# offsets.net
KiCad netlist of a schematic drawn in EAGLE
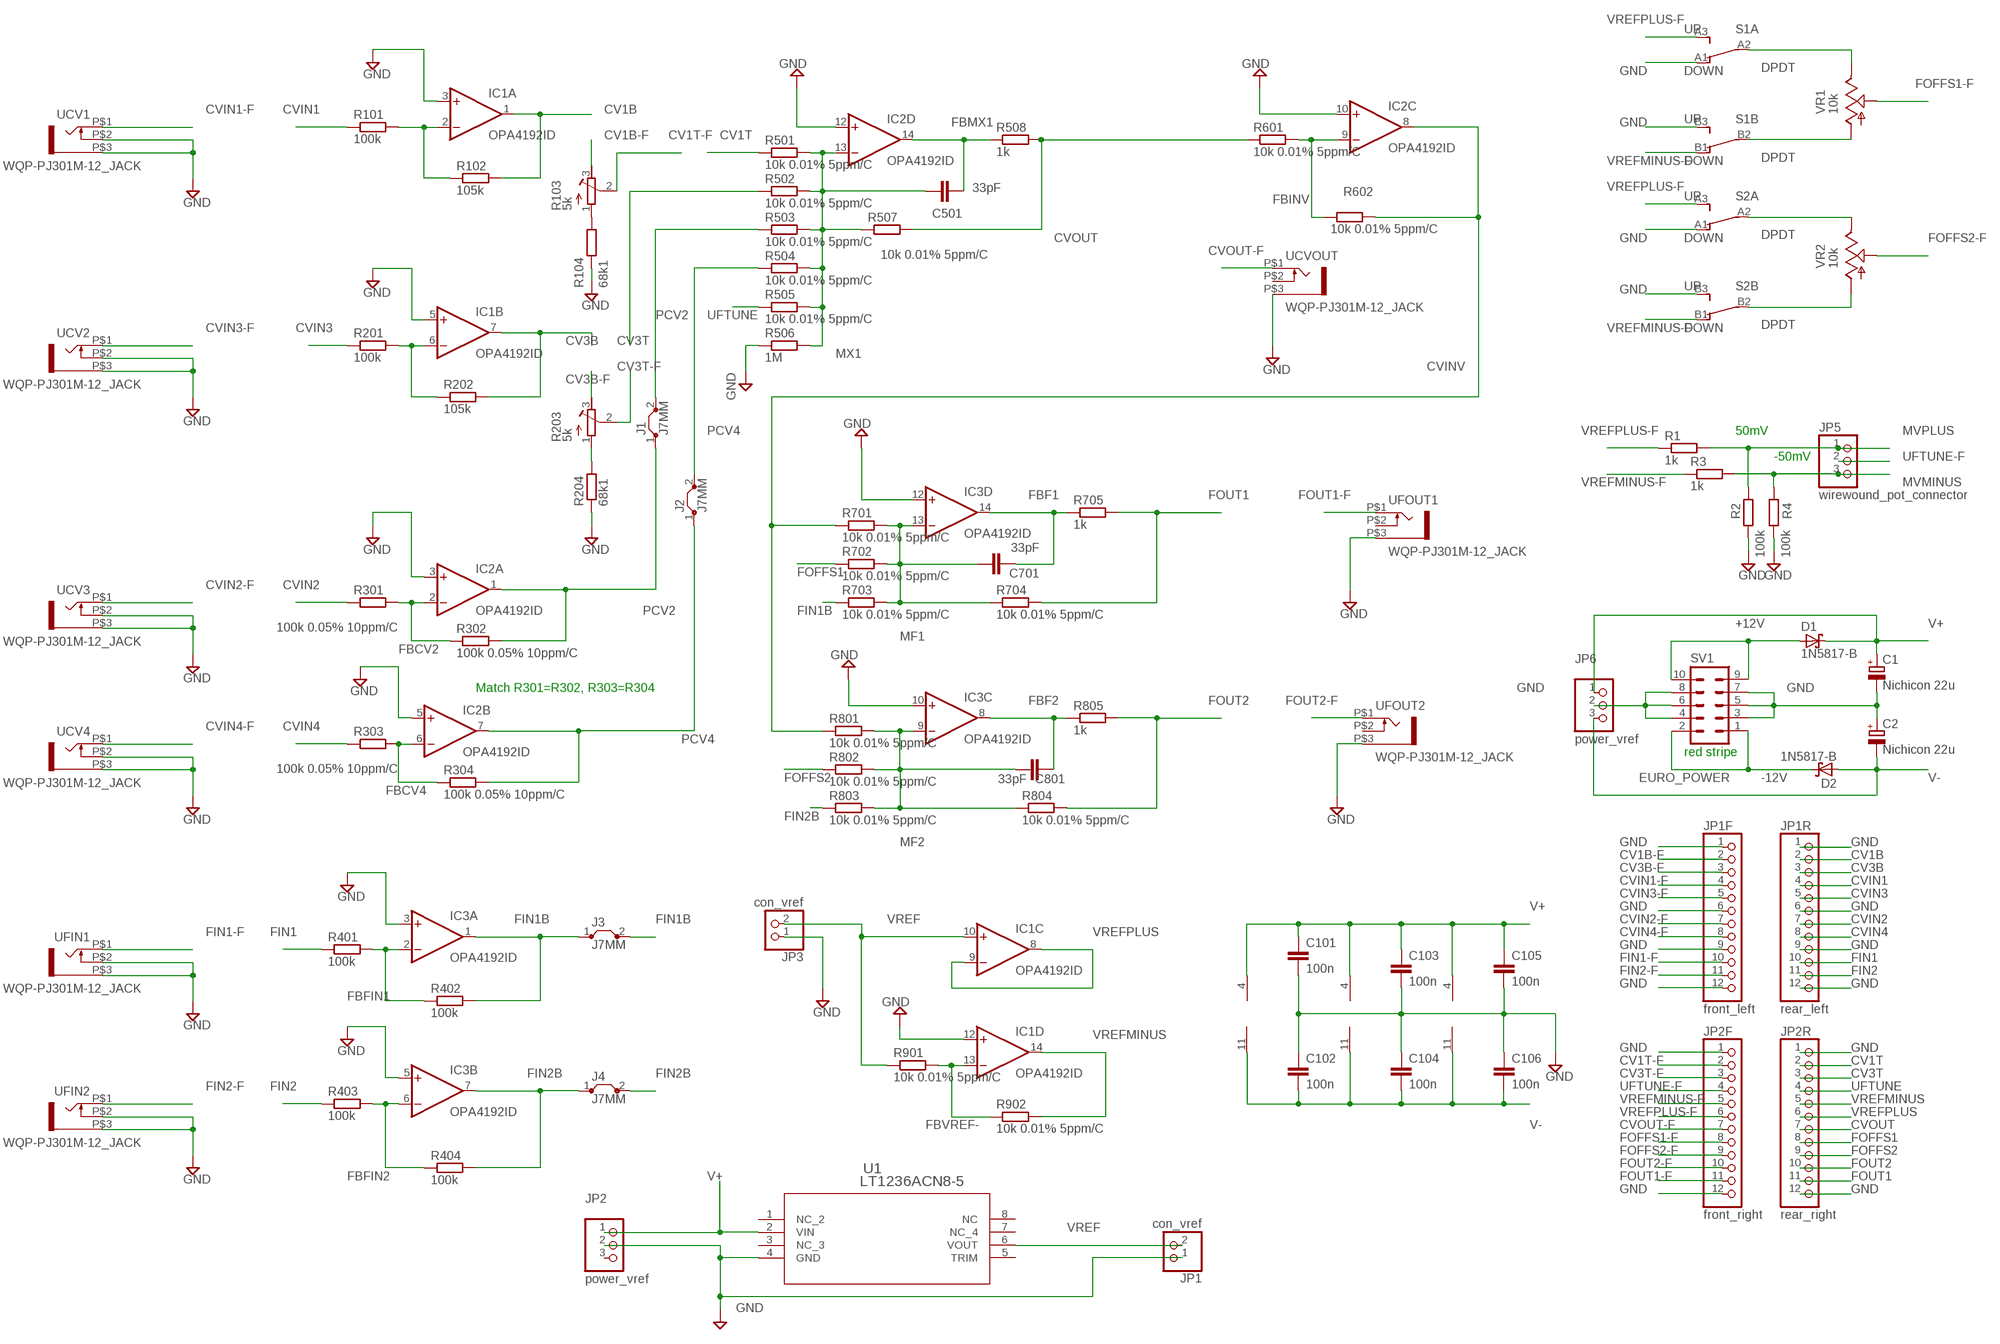
[diagram p0: schematic, sheet 1]

(export (version "E")
  (design (tool "Eeschema 10.0.6"))
  (components
    (comp (ref "C1")
      (value "Nichicon 22u")
      (footprint "eagle-import:E2,5-5")
      (libsource (lib "eagle-import") (part "CPOL-EUE2.5-5"))
    )
    (comp (ref "C2")
      (value "Nichicon 22u")
      (footprint "eagle-import:E2,5-5")
      (libsource (lib "eagle-import") (part "CPOL-EUE2.5-5"))
    )
    (comp (ref "C101")
      (value "100n")
      (footprint "eagle-import:C1206")
      (libsource (lib "eagle-import") (part "C-EUC1206"))
    )
    (comp (ref "C102")
      (value "100n")
      (footprint "eagle-import:C1206")
      (libsource (lib "eagle-import") (part "C-EUC1206"))
    )
    (comp (ref "C103")
      (value "100n")
      (footprint "eagle-import:C1206")
      (libsource (lib "eagle-import") (part "C-EUC1206"))
    )
    (comp (ref "C104")
      (value "100n")
      (footprint "eagle-import:C1206")
      (libsource (lib "eagle-import") (part "C-EUC1206"))
    )
    (comp (ref "C105")
      (value "100n")
      (footprint "eagle-import:C1206")
      (libsource (lib "eagle-import") (part "C-EUC1206"))
    )
    (comp (ref "C106")
      (value "100n")
      (footprint "eagle-import:C1206")
      (libsource (lib "eagle-import") (part "C-EUC1206"))
    )
    (comp (ref "C501")
      (value "33pF")
      (footprint "eagle-import:C0805K")
      (libsource (lib "eagle-import") (part "C-EUC0805K"))
    )
    (comp (ref "C701")
      (value "33pF")
      (footprint "eagle-import:C0805K")
      (libsource (lib "eagle-import") (part "C-EUC0805K"))
    )
    (comp (ref "C801")
      (value "33pF")
      (footprint "eagle-import:C0805K")
      (libsource (lib "eagle-import") (part "C-EUC0805K"))
    )
    (comp (ref "D1")
      (value "1N5817-B")
      (footprint "eagle-import:DO41-7.6")
      (libsource (lib "eagle-import") (part "1N5817-B"))
    )
    (comp (ref "D2")
      (value "1N5817-B")
      (footprint "eagle-import:DO41-7.6")
      (libsource (lib "eagle-import") (part "1N5817-B"))
    )
    (comp (ref "IC1")
      (value "OPA4192ID")
      (footprint "eagle-import:SO14")
      (libsource (lib "eagle-import") (part "TL074D"))
    )
    (comp (ref "IC2")
      (value "OPA4192ID")
      (footprint "eagle-import:SO14")
      (libsource (lib "eagle-import") (part "TL074D"))
    )
    (comp (ref "IC3")
      (value "OPA4192ID")
      (footprint "eagle-import:SO14")
      (libsource (lib "eagle-import") (part "TL074D"))
    )
    (comp (ref "J1")
      (value "J7MM")
      (footprint "eagle-import:07")
      (libsource (lib "eagle-import") (part "J7MM"))
    )
    (comp (ref "J2")
      (value "J7MM")
      (footprint "eagle-import:07")
      (libsource (lib "eagle-import") (part "J7MM"))
    )
    (comp (ref "J3")
      (value "J7MM")
      (footprint "eagle-import:07")
      (libsource (lib "eagle-import") (part "J7MM"))
    )
    (comp (ref "J4")
      (value "J7MM")
      (footprint "eagle-import:07")
      (libsource (lib "eagle-import") (part "J7MM"))
    )
    (comp (ref "JP1")
      (value "con_vref")
      (footprint "eagle-import:1X02")
      (libsource (lib "eagle-import") (part "PINHD-1X2"))
    )
    (comp (ref "JP1F")
      (value "front_left")
      (footprint "eagle-import:1X12")
      (libsource (lib "eagle-import") (part "PINHD-1X12"))
    )
    (comp (ref "JP1R")
      (value "rear_left")
      (footprint "eagle-import:1X12")
      (libsource (lib "eagle-import") (part "PINHD-1X12"))
    )
    (comp (ref "JP2")
      (value "power_vref")
      (footprint "eagle-import:1X03")
      (libsource (lib "eagle-import") (part "PINHD-1X3"))
    )
    (comp (ref "JP2F")
      (value "front_right")
      (footprint "eagle-import:1X12")
      (libsource (lib "eagle-import") (part "PINHD-1X12"))
    )
    (comp (ref "JP2R")
      (value "rear_right")
      (footprint "eagle-import:1X12")
      (libsource (lib "eagle-import") (part "PINHD-1X12"))
    )
    (comp (ref "JP3")
      (value "con_vref")
      (footprint "eagle-import:1X02")
      (libsource (lib "eagle-import") (part "PINHD-1X2"))
    )
    (comp (ref "JP5")
      (value "wirewound_pot_connector")
      (footprint "eagle-import:1X03")
      (libsource (lib "eagle-import") (part "PINHD-1X3"))
    )
    (comp (ref "JP6")
      (value "power_vref")
      (footprint "eagle-import:1X03")
      (libsource (lib "eagle-import") (part "PINHD-1X3"))
    )
    (comp (ref "R1")
      (value "1k")
      (footprint "eagle-import:R0805W")
      (libsource (lib "eagle-import") (part "R-EU_R0805W"))
    )
    (comp (ref "R2")
      (value "100k")
      (footprint "eagle-import:R0805W")
      (libsource (lib "eagle-import") (part "R-EU_R0805W"))
    )
    (comp (ref "R3")
      (value "1k")
      (footprint "eagle-import:R0805W")
      (libsource (lib "eagle-import") (part "R-EU_R0805W"))
    )
    (comp (ref "R4")
      (value "100k")
      (footprint "eagle-import:R0805W")
      (libsource (lib "eagle-import") (part "R-EU_R0805W"))
    )
    (comp (ref "R101")
      (value "100k")
      (footprint "eagle-import:R0805W")
      (libsource (lib "eagle-import") (part "R-EU_R0805W"))
    )
    (comp (ref "R102")
      (value "105k")
      (footprint "eagle-import:R0805W")
      (libsource (lib "eagle-import") (part "R-EU_R0805W"))
    )
    (comp (ref "R103")
      (value "5k")
      (footprint "eagle-import:RTRIM3296W")
      (libsource (lib "eagle-import") (part "R-TRIMM3296W"))
    )
    (comp (ref "R104")
      (value "68k1")
      (footprint "eagle-import:R0805W")
      (libsource (lib "eagle-import") (part "R-EU_R0805W"))
    )
    (comp (ref "R201")
      (value "100k")
      (footprint "eagle-import:R0805W")
      (libsource (lib "eagle-import") (part "R-EU_R0805W"))
    )
    (comp (ref "R202")
      (value "105k")
      (footprint "eagle-import:R0805W")
      (libsource (lib "eagle-import") (part "R-EU_R0805W"))
    )
    (comp (ref "R203")
      (value "5k")
      (footprint "eagle-import:RTRIM3296W")
      (libsource (lib "eagle-import") (part "R-TRIMM3296W"))
    )
    (comp (ref "R204")
      (value "68k1")
      (footprint "eagle-import:R0805W")
      (libsource (lib "eagle-import") (part "R-EU_R0805W"))
    )
    (comp (ref "R301")
      (value "100k 0.05% 10ppm/C")
      (footprint "eagle-import:R0805W")
      (libsource (lib "eagle-import") (part "R-EU_R0805W"))
    )
    (comp (ref "R302")
      (value "100k 0.05% 10ppm/C")
      (footprint "eagle-import:R0805W")
      (libsource (lib "eagle-import") (part "R-EU_R0805W"))
    )
    (comp (ref "R303")
      (value "100k 0.05% 10ppm/C")
      (footprint "eagle-import:R0805W")
      (libsource (lib "eagle-import") (part "R-EU_R0805W"))
    )
    (comp (ref "R304")
      (value "100k 0.05% 10ppm/C")
      (footprint "eagle-import:R0805W")
      (libsource (lib "eagle-import") (part "R-EU_R0805W"))
    )
    (comp (ref "R401")
      (value "100k")
      (footprint "eagle-import:R0805W")
      (libsource (lib "eagle-import") (part "R-EU_R0805W"))
    )
    (comp (ref "R402")
      (value "100k")
      (footprint "eagle-import:R0805W")
      (libsource (lib "eagle-import") (part "R-EU_R0805W"))
    )
    (comp (ref "R403")
      (value "100k")
      (footprint "eagle-import:R0805W")
      (libsource (lib "eagle-import") (part "R-EU_R0805W"))
    )
    (comp (ref "R404")
      (value "100k")
      (footprint "eagle-import:R0805W")
      (libsource (lib "eagle-import") (part "R-EU_R0805W"))
    )
    (comp (ref "R501")
      (value "10k 0.01% 5ppm/C")
      (footprint "eagle-import:R0805W")
      (libsource (lib "eagle-import") (part "R-EU_R0805W"))
    )
    (comp (ref "R502")
      (value "10k 0.01% 5ppm/C")
      (footprint "eagle-import:R0805W")
      (libsource (lib "eagle-import") (part "R-EU_R0805W"))
    )
    (comp (ref "R503")
      (value "10k 0.01% 5ppm/C")
      (footprint "eagle-import:R0805W")
      (libsource (lib "eagle-import") (part "R-EU_R0805W"))
    )
    (comp (ref "R504")
      (value "10k 0.01% 5ppm/C")
      (footprint "eagle-import:R0805W")
      (libsource (lib "eagle-import") (part "R-EU_R0805W"))
    )
    (comp (ref "R505")
      (value "10k 0.01% 5ppm/C")
      (footprint "eagle-import:R0805W")
      (libsource (lib "eagle-import") (part "R-EU_R0805W"))
    )
    (comp (ref "R506")
      (value "1M")
      (footprint "eagle-import:R0805W")
      (libsource (lib "eagle-import") (part "R-EU_R0805W"))
    )
    (comp (ref "R507")
      (value "10k 0.01% 5ppm/C")
      (footprint "eagle-import:R0805W")
      (libsource (lib "eagle-import") (part "R-EU_R0805W"))
    )
    (comp (ref "R508")
      (value "1k")
      (footprint "eagle-import:R0805W")
      (libsource (lib "eagle-import") (part "R-EU_R0805W"))
    )
    (comp (ref "R601")
      (value "10k 0.01% 5ppm/C")
      (footprint "eagle-import:R0805W")
      (libsource (lib "eagle-import") (part "R-EU_R0805W"))
    )
    (comp (ref "R602")
      (value "10k 0.01% 5ppm/C")
      (footprint "eagle-import:R0805W")
      (libsource (lib "eagle-import") (part "R-EU_R0805W"))
    )
    (comp (ref "R701")
      (value "10k 0.01% 5ppm/C")
      (footprint "eagle-import:R0805W")
      (libsource (lib "eagle-import") (part "R-EU_R0805W"))
    )
    (comp (ref "R702")
      (value "10k 0.01% 5ppm/C")
      (footprint "eagle-import:R0805W")
      (libsource (lib "eagle-import") (part "R-EU_R0805W"))
    )
    (comp (ref "R703")
      (value "10k 0.01% 5ppm/C")
      (footprint "eagle-import:R0805W")
      (libsource (lib "eagle-import") (part "R-EU_R0805W"))
    )
    (comp (ref "R704")
      (value "10k 0.01% 5ppm/C")
      (footprint "eagle-import:R0805W")
      (libsource (lib "eagle-import") (part "R-EU_R0805W"))
    )
    (comp (ref "R705")
      (value "1k")
      (footprint "eagle-import:R0805W")
      (libsource (lib "eagle-import") (part "R-EU_R0805W"))
    )
    (comp (ref "R801")
      (value "10k 0.01% 5ppm/C")
      (footprint "eagle-import:R0805W")
      (libsource (lib "eagle-import") (part "R-EU_R0805W"))
    )
    (comp (ref "R802")
      (value "10k 0.01% 5ppm/C")
      (footprint "eagle-import:R0805W")
      (libsource (lib "eagle-import") (part "R-EU_R0805W"))
    )
    (comp (ref "R803")
      (value "10k 0.01% 5ppm/C")
      (footprint "eagle-import:R0805W")
      (libsource (lib "eagle-import") (part "R-EU_R0805W"))
    )
    (comp (ref "R804")
      (value "10k 0.01% 5ppm/C")
      (footprint "eagle-import:R0805W")
      (libsource (lib "eagle-import") (part "R-EU_R0805W"))
    )
    (comp (ref "R805")
      (value "1k")
      (footprint "eagle-import:R0805W")
      (libsource (lib "eagle-import") (part "R-EU_R0805W"))
    )
    (comp (ref "R901")
      (value "10k 0.01% 5ppm/C")
      (footprint "eagle-import:R0805W")
      (libsource (lib "eagle-import") (part "R-EU_R0805W"))
    )
    (comp (ref "R902")
      (value "10k 0.01% 5ppm/C")
      (footprint "eagle-import:R0805W")
      (libsource (lib "eagle-import") (part "R-EU_R0805W"))
    )
    (comp (ref "S1")
      (value "DPDT")
      (footprint "eagle-import:DPDT-VERTICAL-TOP-SUBMINI-MULTICOMP")
      (libsource (lib "eagle-import") (part "DPDT-VERTICAL-DOWNTOP-SUBMINI"))
    )
    (comp (ref "S2")
      (value "DPDT")
      (footprint "eagle-import:DPDT-VERTICAL-TOP-SUBMINI-MULTICOMP")
      (libsource (lib "eagle-import") (part "DPDT-VERTICAL-DOWNTOP-SUBMINI"))
    )
    (comp (ref "SV1")
      (value "EURO_POWER")
      (footprint "eagle-import:EURO_POWER_HEADER")
      (libsource (lib "eagle-import") (part "EURO_POWER_HEADERREGULAR"))
    )
    (comp (ref "U1")
      (value "LT1236ACN8-5")
      (footprint "eagle-import:PDIP-8_N")
      (fields (field (name "MANUFACTURER_PART_NUMBER") "lt1236acn810"))
      (libsource (lib "eagle-import") (part "LT1236ACN8-10"))
    )
    (comp (ref "UCV1")
      (value "WQP-PJ301M-12_JACK")
      (footprint "eagle-import:WQP-PJ301M-12_JACK")
      (libsource (lib "eagle-import") (part "WQP-PJ301M-12_JACK"))
    )
    (comp (ref "UCV2")
      (value "WQP-PJ301M-12_JACK")
      (footprint "eagle-import:WQP-PJ301M-12_JACK")
      (libsource (lib "eagle-import") (part "WQP-PJ301M-12_JACK"))
    )
    (comp (ref "UCV3")
      (value "WQP-PJ301M-12_JACK")
      (footprint "eagle-import:WQP-PJ301M-12_JACK")
      (libsource (lib "eagle-import") (part "WQP-PJ301M-12_JACK"))
    )
    (comp (ref "UCV4")
      (value "WQP-PJ301M-12_JACK")
      (footprint "eagle-import:WQP-PJ301M-12_JACK")
      (libsource (lib "eagle-import") (part "WQP-PJ301M-12_JACK"))
    )
    (comp (ref "UCVOUT")
      (value "WQP-PJ301M-12_JACK")
      (footprint "eagle-import:WQP-PJ301M-12_JACK")
      (libsource (lib "eagle-import") (part "WQP-PJ301M-12_JACK"))
    )
    (comp (ref "UFIN1")
      (value "WQP-PJ301M-12_JACK")
      (footprint "eagle-import:WQP-PJ301M-12_JACK")
      (libsource (lib "eagle-import") (part "WQP-PJ301M-12_JACK"))
    )
    (comp (ref "UFIN2")
      (value "WQP-PJ301M-12_JACK")
      (footprint "eagle-import:WQP-PJ301M-12_JACK")
      (libsource (lib "eagle-import") (part "WQP-PJ301M-12_JACK"))
    )
    (comp (ref "UFOUT1")
      (value "WQP-PJ301M-12_JACK")
      (footprint "eagle-import:WQP-PJ301M-12_JACK")
      (libsource (lib "eagle-import") (part "WQP-PJ301M-12_JACK"))
    )
    (comp (ref "UFOUT2")
      (value "WQP-PJ301M-12_JACK")
      (footprint "eagle-import:WQP-PJ301M-12_JACK")
      (libsource (lib "eagle-import") (part "WQP-PJ301M-12_JACK"))
    )
    (comp (ref "VR1")
      (value "10k")
      (footprint "eagle-import:9MM_SNAP-IN_POT")
      (libsource (lib "eagle-import") (part "9MM_SNAP-IN_POT_"))
    )
    (comp (ref "VR2")
      (value "10k")
      (footprint "eagle-import:9MM_SNAP-IN_POT")
      (libsource (lib "eagle-import") (part "9MM_SNAP-IN_POT_"))
    )
  )
  (nets
    (net (code "1") (name "/+12V") (class "Default")
      (node (ref "D1") (pin "A") (pinfunction "A_A") (pintype "passive"))
      (node (ref "SV1") (pin "10") (pinfunction "10_10") (pintype "passive"))
      (node (ref "SV1") (pin "9") (pinfunction "9_9") (pintype "passive"))
    )
    (net (code "2") (name "/-12V") (class "Default")
      (node (ref "D2") (pin "C") (pinfunction "C_C") (pintype "passive"))
      (node (ref "SV1") (pin "1") (pinfunction "1_1") (pintype "passive"))
      (node (ref "SV1") (pin "2") (pinfunction "2_2") (pintype "passive"))
    )
    (net (code "3") (name "/CV1B") (class "Default")
      (node (ref "IC1") (pin "1") (pinfunction "OUT_1") (pintype "output"))
      (node (ref "JP1R") (pin "2") (pinfunction "2_2") (pintype "passive"))
      (node (ref "R102") (pin "2") (pinfunction "2_2") (pintype "passive"))
    )
    (net (code "4") (name "/CV1B-F") (class "Default")
      (node (ref "JP1F") (pin "2") (pinfunction "2_2") (pintype "passive"))
      (node (ref "R103") (pin "3") (pinfunction "E_3") (pintype "passive"))
    )
    (net (code "5") (name "/CV1T") (class "Default")
      (node (ref "JP2R") (pin "2") (pinfunction "2_2") (pintype "passive"))
      (node (ref "R501") (pin "1") (pinfunction "1_1") (pintype "passive"))
    )
    (net (code "6") (name "/CV1T-F") (class "Default")
      (node (ref "JP2F") (pin "2") (pinfunction "2_2") (pintype "passive"))
      (node (ref "R103") (pin "2") (pinfunction "S_2") (pintype "passive"))
    )
    (net (code "7") (name "/CV3B") (class "Default")
      (node (ref "IC1") (pin "7") (pinfunction "OUT_7") (pintype "output"))
      (node (ref "JP1R") (pin "3") (pinfunction "3_3") (pintype "passive"))
      (node (ref "R202") (pin "2") (pinfunction "2_2") (pintype "passive"))
    )
    (net (code "8") (name "/CV3B-F") (class "Default")
      (node (ref "JP1F") (pin "3") (pinfunction "3_3") (pintype "passive"))
      (node (ref "R203") (pin "3") (pinfunction "E_3") (pintype "passive"))
    )
    (net (code "9") (name "/CV3T") (class "Default")
      (node (ref "JP2R") (pin "3") (pinfunction "3_3") (pintype "passive"))
      (node (ref "R502") (pin "1") (pinfunction "1_1") (pintype "passive"))
    )
    (net (code "10") (name "/CV3T-F") (class "Default")
      (node (ref "JP2F") (pin "3") (pinfunction "3_3") (pintype "passive"))
      (node (ref "R203") (pin "2") (pinfunction "S_2") (pintype "passive"))
    )
    (net (code "11") (name "/CVIN1") (class "Default")
      (node (ref "JP1R") (pin "4") (pinfunction "4_4") (pintype "passive"))
      (node (ref "R101") (pin "1") (pinfunction "1_1") (pintype "passive"))
    )
    (net (code "12") (name "/CVIN1-F") (class "Default")
      (node (ref "JP1F") (pin "4") (pinfunction "4_4") (pintype "passive"))
      (node (ref "UCV1") (pin "P$1") (pinfunction "2_P$1") (pintype "passive"))
    )
    (net (code "13") (name "/CVIN2") (class "Default")
      (node (ref "JP1R") (pin "7") (pinfunction "7_7") (pintype "passive"))
      (node (ref "R301") (pin "1") (pinfunction "1_1") (pintype "passive"))
    )
    (net (code "14") (name "/CVIN2-F") (class "Default")
      (node (ref "JP1F") (pin "7") (pinfunction "7_7") (pintype "passive"))
      (node (ref "UCV3") (pin "P$1") (pinfunction "2_P$1") (pintype "passive"))
    )
    (net (code "15") (name "/CVIN3") (class "Default")
      (node (ref "JP1R") (pin "5") (pinfunction "5_5") (pintype "passive"))
      (node (ref "R201") (pin "1") (pinfunction "1_1") (pintype "passive"))
    )
    (net (code "16") (name "/CVIN3-F") (class "Default")
      (node (ref "JP1F") (pin "5") (pinfunction "5_5") (pintype "passive"))
      (node (ref "UCV2") (pin "P$1") (pinfunction "2_P$1") (pintype "passive"))
    )
    (net (code "17") (name "/CVIN4") (class "Default")
      (node (ref "JP1R") (pin "8") (pinfunction "8_8") (pintype "passive"))
      (node (ref "R303") (pin "1") (pinfunction "1_1") (pintype "passive"))
    )
    (net (code "18") (name "/CVIN4-F") (class "Default")
      (node (ref "JP1F") (pin "8") (pinfunction "8_8") (pintype "passive"))
      (node (ref "UCV4") (pin "P$1") (pinfunction "2_P$1") (pintype "passive"))
    )
    (net (code "19") (name "/CVINV") (class "Default")
      (node (ref "IC2") (pin "8") (pinfunction "OUT_8") (pintype "output"))
      (node (ref "R602") (pin "2") (pinfunction "2_2") (pintype "passive"))
      (node (ref "R701") (pin "1") (pinfunction "1_1") (pintype "passive"))
      (node (ref "R801") (pin "1") (pinfunction "1_1") (pintype "passive"))
    )
    (net (code "20") (name "/CVOUT") (class "Default")
      (node (ref "JP2R") (pin "7") (pinfunction "7_7") (pintype "passive"))
      (node (ref "R507") (pin "2") (pinfunction "2_2") (pintype "passive"))
      (node (ref "R508") (pin "2") (pinfunction "2_2") (pintype "passive"))
      (node (ref "R601") (pin "1") (pinfunction "1_1") (pintype "passive"))
    )
    (net (code "21") (name "/CVOUT-F") (class "Default")
      (node (ref "JP2F") (pin "7") (pinfunction "7_7") (pintype "passive"))
      (node (ref "UCVOUT") (pin "P$1") (pinfunction "2_P$1") (pintype "passive"))
    )
    (net (code "22") (name "/FBCV2") (class "Default")
      (node (ref "IC2") (pin "2") (pinfunction "-IN_2") (pintype "input"))
      (node (ref "R301") (pin "2") (pinfunction "2_2") (pintype "passive"))
      (node (ref "R302") (pin "1") (pinfunction "1_1") (pintype "passive"))
    )
    (net (code "23") (name "/FBCV4") (class "Default")
      (node (ref "IC2") (pin "6") (pinfunction "-IN_6") (pintype "input"))
      (node (ref "R303") (pin "2") (pinfunction "2_2") (pintype "passive"))
      (node (ref "R304") (pin "1") (pinfunction "1_1") (pintype "passive"))
    )
    (net (code "24") (name "/FBF1") (class "Default")
      (node (ref "C701") (pin "2") (pinfunction "2_2") (pintype "passive"))
      (node (ref "IC3") (pin "14") (pinfunction "OUT_14") (pintype "output"))
      (node (ref "R705") (pin "1") (pinfunction "1_1") (pintype "passive"))
    )
    (net (code "25") (name "/FBF2") (class "Default")
      (node (ref "C801") (pin "2") (pinfunction "2_2") (pintype "passive"))
      (node (ref "IC3") (pin "8") (pinfunction "OUT_8") (pintype "output"))
      (node (ref "R805") (pin "1") (pinfunction "1_1") (pintype "passive"))
    )
    (net (code "26") (name "/FBFIN1") (class "Default")
      (node (ref "IC3") (pin "2") (pinfunction "-IN_2") (pintype "input"))
      (node (ref "R401") (pin "2") (pinfunction "2_2") (pintype "passive"))
      (node (ref "R402") (pin "1") (pinfunction "1_1") (pintype "passive"))
    )
    (net (code "27") (name "/FBFIN2") (class "Default")
      (node (ref "IC3") (pin "6") (pinfunction "-IN_6") (pintype "input"))
      (node (ref "R403") (pin "2") (pinfunction "2_2") (pintype "passive"))
      (node (ref "R404") (pin "1") (pinfunction "1_1") (pintype "passive"))
    )
    (net (code "28") (name "/FBINV") (class "Default")
      (node (ref "IC2") (pin "9") (pinfunction "-IN_9") (pintype "input"))
      (node (ref "R601") (pin "2") (pinfunction "2_2") (pintype "passive"))
      (node (ref "R602") (pin "1") (pinfunction "1_1") (pintype "passive"))
    )
    (net (code "29") (name "/FBMX1") (class "Default")
      (node (ref "C501") (pin "2") (pinfunction "2_2") (pintype "passive"))
      (node (ref "IC2") (pin "14") (pinfunction "OUT_14") (pintype "output"))
      (node (ref "R508") (pin "1") (pinfunction "1_1") (pintype "passive"))
    )
    (net (code "30") (name "/FBVREF-") (class "Default")
      (node (ref "IC1") (pin "13") (pinfunction "-IN_13") (pintype "input"))
      (node (ref "R901") (pin "2") (pinfunction "2_2") (pintype "passive"))
      (node (ref "R902") (pin "1") (pinfunction "1_1") (pintype "passive"))
    )
    (net (code "31") (name "/FIN1") (class "Default")
      (node (ref "JP1R") (pin "10") (pinfunction "10_10") (pintype "passive"))
      (node (ref "R401") (pin "1") (pinfunction "1_1") (pintype "passive"))
    )
    (net (code "32") (name "/FIN1-F") (class "Default")
      (node (ref "JP1F") (pin "10") (pinfunction "10_10") (pintype "passive"))
      (node (ref "UFIN1") (pin "P$1") (pinfunction "2_P$1") (pintype "passive"))
    )
    (net (code "33") (name "/FIN1B") (class "Default")
      (node (ref "IC3") (pin "1") (pinfunction "OUT_1") (pintype "output"))
      (node (ref "J3") (pin "1") (pinfunction "1_1") (pintype "passive"))
      (node (ref "J3") (pin "2") (pinfunction "2_2") (pintype "passive"))
      (node (ref "R402") (pin "2") (pinfunction "2_2") (pintype "passive"))
      (node (ref "R703") (pin "1") (pinfunction "1_1") (pintype "passive"))
    )
    (net (code "34") (name "/FIN2") (class "Default")
      (node (ref "JP1R") (pin "11") (pinfunction "11_11") (pintype "passive"))
      (node (ref "R403") (pin "1") (pinfunction "1_1") (pintype "passive"))
    )
    (net (code "35") (name "/FIN2-F") (class "Default")
      (node (ref "JP1F") (pin "11") (pinfunction "11_11") (pintype "passive"))
      (node (ref "UFIN2") (pin "P$1") (pinfunction "2_P$1") (pintype "passive"))
    )
    (net (code "36") (name "/FIN2B") (class "Default")
      (node (ref "IC3") (pin "7") (pinfunction "OUT_7") (pintype "output"))
      (node (ref "J4") (pin "1") (pinfunction "1_1") (pintype "passive"))
      (node (ref "J4") (pin "2") (pinfunction "2_2") (pintype "passive"))
      (node (ref "R404") (pin "2") (pinfunction "2_2") (pintype "passive"))
      (node (ref "R803") (pin "1") (pinfunction "1_1") (pintype "passive"))
    )
    (net (code "37") (name "/FOFFS1") (class "Default")
      (node (ref "JP2R") (pin "8") (pinfunction "8_8") (pintype "passive"))
      (node (ref "R702") (pin "1") (pinfunction "1_1") (pintype "passive"))
    )
    (net (code "38") (name "/FOFFS1-F") (class "Default")
      (node (ref "JP2F") (pin "8") (pinfunction "8_8") (pintype "passive"))
      (node (ref "VR1") (pin "2") (pinfunction "S_2") (pintype "passive"))
    )
    (net (code "39") (name "/FOFFS2") (class "Default")
      (node (ref "JP2R") (pin "9") (pinfunction "9_9") (pintype "passive"))
      (node (ref "R802") (pin "1") (pinfunction "1_1") (pintype "passive"))
    )
    (net (code "40") (name "/FOFFS2-F") (class "Default")
      (node (ref "JP2F") (pin "9") (pinfunction "9_9") (pintype "passive"))
      (node (ref "VR2") (pin "2") (pinfunction "S_2") (pintype "passive"))
    )
    (net (code "41") (name "/FOUT1") (class "Default")
      (node (ref "JP2R") (pin "11") (pinfunction "11_11") (pintype "passive"))
      (node (ref "R704") (pin "2") (pinfunction "2_2") (pintype "passive"))
      (node (ref "R705") (pin "2") (pinfunction "2_2") (pintype "passive"))
    )
    (net (code "42") (name "/FOUT1-F") (class "Default")
      (node (ref "JP2F") (pin "11") (pinfunction "11_11") (pintype "passive"))
      (node (ref "UFOUT1") (pin "P$1") (pinfunction "2_P$1") (pintype "passive"))
    )
    (net (code "43") (name "/FOUT2") (class "Default")
      (node (ref "JP2R") (pin "10") (pinfunction "10_10") (pintype "passive"))
      (node (ref "R804") (pin "2") (pinfunction "2_2") (pintype "passive"))
      (node (ref "R805") (pin "2") (pinfunction "2_2") (pintype "passive"))
    )
    (net (code "44") (name "/FOUT2-F") (class "Default")
      (node (ref "JP2F") (pin "10") (pinfunction "10_10") (pintype "passive"))
      (node (ref "UFOUT2") (pin "P$1") (pinfunction "2_P$1") (pintype "passive"))
    )
    (net (code "45") (name "/MF1") (class "Default")
      (node (ref "C701") (pin "1") (pinfunction "1_1") (pintype "passive"))
      (node (ref "IC3") (pin "13") (pinfunction "-IN_13") (pintype "input"))
      (node (ref "R701") (pin "2") (pinfunction "2_2") (pintype "passive"))
      (node (ref "R702") (pin "2") (pinfunction "2_2") (pintype "passive"))
      (node (ref "R703") (pin "2") (pinfunction "2_2") (pintype "passive"))
      (node (ref "R704") (pin "1") (pinfunction "1_1") (pintype "passive"))
    )
    (net (code "46") (name "/MF2") (class "Default")
      (node (ref "C801") (pin "1") (pinfunction "1_1") (pintype "passive"))
      (node (ref "IC3") (pin "9") (pinfunction "-IN_9") (pintype "input"))
      (node (ref "R801") (pin "2") (pinfunction "2_2") (pintype "passive"))
      (node (ref "R802") (pin "2") (pinfunction "2_2") (pintype "passive"))
      (node (ref "R803") (pin "2") (pinfunction "2_2") (pintype "passive"))
      (node (ref "R804") (pin "1") (pinfunction "1_1") (pintype "passive"))
    )
    (net (code "47") (name "/MVMINUS") (class "Default")
      (node (ref "JP5") (pin "3") (pinfunction "3_3") (pintype "passive"))
      (node (ref "R3") (pin "2") (pinfunction "2_2") (pintype "passive"))
      (node (ref "R4") (pin "2") (pinfunction "2_2") (pintype "passive"))
    )
    (net (code "48") (name "/MVPLUS") (class "Default")
      (node (ref "JP5") (pin "1") (pinfunction "1_1") (pintype "passive"))
      (node (ref "R1") (pin "2") (pinfunction "2_2") (pintype "passive"))
      (node (ref "R2") (pin "2") (pinfunction "2_2") (pintype "passive"))
    )
    (net (code "49") (name "/MX1") (class "Default")
      (node (ref "C501") (pin "1") (pinfunction "1_1") (pintype "passive"))
      (node (ref "IC2") (pin "13") (pinfunction "-IN_13") (pintype "input"))
      (node (ref "R501") (pin "2") (pinfunction "2_2") (pintype "passive"))
      (node (ref "R502") (pin "2") (pinfunction "2_2") (pintype "passive"))
      (node (ref "R503") (pin "2") (pinfunction "2_2") (pintype "passive"))
      (node (ref "R504") (pin "2") (pinfunction "2_2") (pintype "passive"))
      (node (ref "R505") (pin "2") (pinfunction "2_2") (pintype "passive"))
      (node (ref "R506") (pin "2") (pinfunction "2_2") (pintype "passive"))
      (node (ref "R507") (pin "1") (pinfunction "1_1") (pintype "passive"))
    )
    (net (code "50") (name "/PCV2") (class "Default")
      (node (ref "IC2") (pin "1") (pinfunction "OUT_1") (pintype "output"))
      (node (ref "J1") (pin "1") (pinfunction "1_1") (pintype "passive"))
      (node (ref "J1") (pin "2") (pinfunction "2_2") (pintype "passive"))
      (node (ref "R302") (pin "2") (pinfunction "2_2") (pintype "passive"))
      (node (ref "R503") (pin "1") (pinfunction "1_1") (pintype "passive"))
    )
    (net (code "51") (name "/PCV4") (class "Default")
      (node (ref "IC2") (pin "7") (pinfunction "OUT_7") (pintype "output"))
      (node (ref "J2") (pin "1") (pinfunction "1_1") (pintype "passive"))
      (node (ref "J2") (pin "2") (pinfunction "2_2") (pintype "passive"))
      (node (ref "R304") (pin "2") (pinfunction "2_2") (pintype "passive"))
      (node (ref "R504") (pin "1") (pinfunction "1_1") (pintype "passive"))
    )
    (net (code "52") (name "/UFTUNE") (class "Default")
      (node (ref "JP2R") (pin "4") (pinfunction "4_4") (pintype "passive"))
      (node (ref "R505") (pin "1") (pinfunction "1_1") (pintype "passive"))
    )
    (net (code "53") (name "/UFTUNE-F") (class "Default")
      (node (ref "JP2F") (pin "4") (pinfunction "4_4") (pintype "passive"))
      (node (ref "JP5") (pin "2") (pinfunction "2_2") (pintype "passive"))
    )
    (net (code "54") (name "/V+") (class "Default")
      (node (ref "C1") (pin "+") (pinfunction "+_+") (pintype "passive"))
      (node (ref "C101") (pin "1") (pinfunction "1_1") (pintype "passive"))
      (node (ref "C103") (pin "1") (pinfunction "1_1") (pintype "passive"))
      (node (ref "C105") (pin "1") (pinfunction "1_1") (pintype "passive"))
      (node (ref "D1") (pin "C") (pinfunction "C_C") (pintype "passive"))
      (node (ref "IC1") (pin "4") (pinfunction "V+_4") (pintype "power_in"))
      (node (ref "IC2") (pin "4") (pinfunction "V+_4") (pintype "power_in"))
      (node (ref "IC3") (pin "4") (pinfunction "V+_4") (pintype "power_in"))
      (node (ref "JP2") (pin "1") (pinfunction "1_1") (pintype "passive"))
      (node (ref "JP6") (pin "1") (pinfunction "1_1") (pintype "passive"))
      (node (ref "U1") (pin "2") (pinfunction "VIN_2") (pintype "input"))
    )
    (net (code "55") (name "/V-") (class "Default")
      (node (ref "C102") (pin "2") (pinfunction "2_2") (pintype "passive"))
      (node (ref "C104") (pin "2") (pinfunction "2_2") (pintype "passive"))
      (node (ref "C106") (pin "2") (pinfunction "2_2") (pintype "passive"))
      (node (ref "C2") (pin "-") (pinfunction "-_-") (pintype "passive"))
      (node (ref "D2") (pin "A") (pinfunction "A_A") (pintype "passive"))
      (node (ref "IC1") (pin "11") (pinfunction "V-_11") (pintype "power_in"))
      (node (ref "IC2") (pin "11") (pinfunction "V-_11") (pintype "power_in"))
      (node (ref "IC3") (pin "11") (pinfunction "V-_11") (pintype "power_in"))
      (node (ref "JP6") (pin "3") (pinfunction "3_3") (pintype "passive"))
    )
    (net (code "56") (name "/VREF") (class "Default")
      (node (ref "IC1") (pin "10") (pinfunction "+IN_10") (pintype "input"))
      (node (ref "JP1") (pin "2") (pinfunction "2_2") (pintype "passive"))
      (node (ref "JP3") (pin "2") (pinfunction "2_2") (pintype "passive"))
      (node (ref "R901") (pin "1") (pinfunction "1_1") (pintype "passive"))
      (node (ref "U1") (pin "6") (pinfunction "VOUT_6") (pintype "output"))
    )
    (net (code "57") (name "/VREFMINUS") (class "Default")
      (node (ref "IC1") (pin "14") (pinfunction "OUT_14") (pintype "output"))
      (node (ref "JP2R") (pin "5") (pinfunction "5_5") (pintype "passive"))
      (node (ref "R902") (pin "2") (pinfunction "2_2") (pintype "passive"))
    )
    (net (code "58") (name "/VREFMINUS-F") (class "Default")
      (node (ref "JP2F") (pin "5") (pinfunction "5_5") (pintype "passive"))
      (node (ref "R3") (pin "1") (pinfunction "1_1") (pintype "passive"))
      (node (ref "S1") (pin "B1") (pinfunction "1_B1") (pintype "passive"))
      (node (ref "S2") (pin "B1") (pinfunction "1_B1") (pintype "passive"))
    )
    (net (code "59") (name "/VREFPLUS") (class "Default")
      (node (ref "IC1") (pin "8") (pinfunction "OUT_8") (pintype "output"))
      (node (ref "IC1") (pin "9") (pinfunction "-IN_9") (pintype "input"))
      (node (ref "JP2R") (pin "6") (pinfunction "6_6") (pintype "passive"))
    )
    (net (code "60") (name "/VREFPLUS-F") (class "Default")
      (node (ref "JP2F") (pin "6") (pinfunction "6_6") (pintype "passive"))
      (node (ref "R1") (pin "1") (pinfunction "1_1") (pintype "passive"))
      (node (ref "S1") (pin "A3") (pinfunction "3_A3") (pintype "passive"))
      (node (ref "S2") (pin "A3") (pinfunction "3_A3") (pintype "passive"))
    )
    (net (code "61") (name "GND") (class "Default")
      (node (ref "C1") (pin "-") (pinfunction "-_-") (pintype "passive"))
      (node (ref "C101") (pin "2") (pinfunction "2_2") (pintype "passive"))
      (node (ref "C102") (pin "1") (pinfunction "1_1") (pintype "passive"))
      (node (ref "C103") (pin "2") (pinfunction "2_2") (pintype "passive"))
      (node (ref "C104") (pin "1") (pinfunction "1_1") (pintype "passive"))
      (node (ref "C105") (pin "2") (pinfunction "2_2") (pintype "passive"))
      (node (ref "C106") (pin "1") (pinfunction "1_1") (pintype "passive"))
      (node (ref "C2") (pin "+") (pinfunction "+_+") (pintype "passive"))
      (node (ref "IC1") (pin "12") (pinfunction "+IN_12") (pintype "input"))
      (node (ref "IC1") (pin "3") (pinfunction "+IN_3") (pintype "input"))
      (node (ref "IC1") (pin "5") (pinfunction "+IN_5") (pintype "input"))
      (node (ref "IC2") (pin "10") (pinfunction "+IN_10") (pintype "input"))
      (node (ref "IC2") (pin "12") (pinfunction "+IN_12") (pintype "input"))
      (node (ref "IC2") (pin "3") (pinfunction "+IN_3") (pintype "input"))
      (node (ref "IC2") (pin "5") (pinfunction "+IN_5") (pintype "input"))
      (node (ref "IC3") (pin "10") (pinfunction "+IN_10") (pintype "input"))
      (node (ref "IC3") (pin "12") (pinfunction "+IN_12") (pintype "input"))
      (node (ref "IC3") (pin "3") (pinfunction "+IN_3") (pintype "input"))
      (node (ref "IC3") (pin "5") (pinfunction "+IN_5") (pintype "input"))
      (node (ref "JP1") (pin "1") (pinfunction "1_1") (pintype "passive"))
      (node (ref "JP1F") (pin "1") (pinfunction "1_1") (pintype "passive"))
      (node (ref "JP1F") (pin "12") (pinfunction "12_12") (pintype "passive"))
      (node (ref "JP1F") (pin "6") (pinfunction "6_6") (pintype "passive"))
      (node (ref "JP1F") (pin "9") (pinfunction "9_9") (pintype "passive"))
      (node (ref "JP1R") (pin "1") (pinfunction "1_1") (pintype "passive"))
      (node (ref "JP1R") (pin "12") (pinfunction "12_12") (pintype "passive"))
      (node (ref "JP1R") (pin "6") (pinfunction "6_6") (pintype "passive"))
      (node (ref "JP1R") (pin "9") (pinfunction "9_9") (pintype "passive"))
      (node (ref "JP2") (pin "2") (pinfunction "2_2") (pintype "passive"))
      (node (ref "JP2F") (pin "1") (pinfunction "1_1") (pintype "passive"))
      (node (ref "JP2F") (pin "12") (pinfunction "12_12") (pintype "passive"))
      (node (ref "JP2R") (pin "1") (pinfunction "1_1") (pintype "passive"))
      (node (ref "JP2R") (pin "12") (pinfunction "12_12") (pintype "passive"))
      (node (ref "JP3") (pin "1") (pinfunction "1_1") (pintype "passive"))
      (node (ref "JP6") (pin "2") (pinfunction "2_2") (pintype "passive"))
      (node (ref "R104") (pin "1") (pinfunction "1_1") (pintype "passive"))
      (node (ref "R2") (pin "1") (pinfunction "1_1") (pintype "passive"))
      (node (ref "R204") (pin "1") (pinfunction "1_1") (pintype "passive"))
      (node (ref "R4") (pin "1") (pinfunction "1_1") (pintype "passive"))
      (node (ref "R506") (pin "1") (pinfunction "1_1") (pintype "passive"))
      (node (ref "S1") (pin "A1") (pinfunction "1_A1") (pintype "passive"))
      (node (ref "S1") (pin "B3") (pinfunction "3_B3") (pintype "passive"))
      (node (ref "S2") (pin "A1") (pinfunction "1_A1") (pintype "passive"))
      (node (ref "S2") (pin "B3") (pinfunction "3_B3") (pintype "passive"))
      (node (ref "SV1") (pin "3") (pinfunction "3_3") (pintype "passive"))
      (node (ref "SV1") (pin "4") (pinfunction "4_4") (pintype "passive"))
      (node (ref "SV1") (pin "5") (pinfunction "5_5") (pintype "passive"))
      (node (ref "SV1") (pin "6") (pinfunction "6_6") (pintype "passive"))
      (node (ref "SV1") (pin "7") (pinfunction "7_7") (pintype "passive"))
      (node (ref "SV1") (pin "8") (pinfunction "8_8") (pintype "passive"))
      (node (ref "U1") (pin "4") (pinfunction "GND_4") (pintype "power_in"))
      (node (ref "UCV1") (pin "P$2") (pinfunction "3_P$2") (pintype "passive"))
      (node (ref "UCV1") (pin "P$3") (pinfunction "1_P$3") (pintype "passive"))
      (node (ref "UCV2") (pin "P$2") (pinfunction "3_P$2") (pintype "passive"))
      (node (ref "UCV2") (pin "P$3") (pinfunction "1_P$3") (pintype "passive"))
      (node (ref "UCV3") (pin "P$2") (pinfunction "3_P$2") (pintype "passive"))
      (node (ref "UCV3") (pin "P$3") (pinfunction "1_P$3") (pintype "passive"))
      (node (ref "UCV4") (pin "P$2") (pinfunction "3_P$2") (pintype "passive"))
      (node (ref "UCV4") (pin "P$3") (pinfunction "1_P$3") (pintype "passive"))
      (node (ref "UCVOUT") (pin "P$3") (pinfunction "1_P$3") (pintype "passive"))
      (node (ref "UFIN1") (pin "P$2") (pinfunction "3_P$2") (pintype "passive"))
      (node (ref "UFIN1") (pin "P$3") (pinfunction "1_P$3") (pintype "passive"))
      (node (ref "UFIN2") (pin "P$2") (pinfunction "3_P$2") (pintype "passive"))
      (node (ref "UFIN2") (pin "P$3") (pinfunction "1_P$3") (pintype "passive"))
      (node (ref "UFOUT1") (pin "P$3") (pinfunction "1_P$3") (pintype "passive"))
      (node (ref "UFOUT2") (pin "P$3") (pinfunction "1_P$3") (pintype "passive"))
    )
    (net (code "62") (name "Net-(IC1A--IN)") (class "Default")
      (node (ref "IC1") (pin "2") (pinfunction "-IN_2") (pintype "input"))
      (node (ref "R101") (pin "2") (pinfunction "2_2") (pintype "passive"))
      (node (ref "R102") (pin "1") (pinfunction "1_1") (pintype "passive"))
    )
    (net (code "63") (name "Net-(IC1B--IN)") (class "Default")
      (node (ref "IC1") (pin "6") (pinfunction "-IN_6") (pintype "input"))
      (node (ref "R201") (pin "2") (pinfunction "2_2") (pintype "passive"))
      (node (ref "R202") (pin "1") (pinfunction "1_1") (pintype "passive"))
    )
    (net (code "64") (name "Net-(R103-A)") (class "Default")
      (node (ref "R103") (pin "1") (pinfunction "A_1") (pintype "passive"))
      (node (ref "R104") (pin "2") (pinfunction "2_2") (pintype "passive"))
    )
    (net (code "65") (name "Net-(R203-A)") (class "Default")
      (node (ref "R203") (pin "1") (pinfunction "A_1") (pintype "passive"))
      (node (ref "R204") (pin "2") (pinfunction "2_2") (pintype "passive"))
    )
    (net (code "66") (name "Net-(S1A-2)") (class "Default")
      (node (ref "S1") (pin "A2") (pinfunction "2_A2") (pintype "passive"))
      (node (ref "VR1") (pin "3") (pinfunction "E_3") (pintype "passive"))
    )
    (net (code "67") (name "Net-(S1B-2)") (class "Default")
      (node (ref "S1") (pin "B2") (pinfunction "2_B2") (pintype "passive"))
      (node (ref "VR1") (pin "1") (pinfunction "A_1") (pintype "passive"))
    )
    (net (code "68") (name "Net-(S2A-2)") (class "Default")
      (node (ref "S2") (pin "A2") (pinfunction "2_A2") (pintype "passive"))
      (node (ref "VR2") (pin "3") (pinfunction "E_3") (pintype "passive"))
    )
    (net (code "69") (name "Net-(S2B-2)") (class "Default")
      (node (ref "S2") (pin "B2") (pinfunction "2_B2") (pintype "passive"))
      (node (ref "VR2") (pin "1") (pinfunction "A_1") (pintype "passive"))
    )
    (net (code "70") (name "unconnected-(JP2-Pad3)") (class "Default")
      (node (ref "JP2") (pin "3") (pinfunction "3_3") (pintype "passive"))
    )
    (net (code "71") (name "unconnected-(U1-NC-Pad8)") (class "Default")
      (node (ref "U1") (pin "8") (pinfunction "NC_8") (pintype "no_connect"))
    )
    (net (code "72") (name "unconnected-(U1-NC_2-Pad1)") (class "Default")
      (node (ref "U1") (pin "1") (pinfunction "NC_2_1") (pintype "no_connect"))
    )
    (net (code "73") (name "unconnected-(U1-NC_3-Pad3)") (class "Default")
      (node (ref "U1") (pin "3") (pinfunction "NC_3_3") (pintype "no_connect"))
    )
    (net (code "74") (name "unconnected-(U1-NC_4-Pad7)") (class "Default")
      (node (ref "U1") (pin "7") (pinfunction "NC_4_7") (pintype "no_connect"))
    )
    (net (code "75") (name "unconnected-(U1-TRIM-Pad5)") (class "Default")
      (node (ref "U1") (pin "5") (pinfunction "TRIM_5") (pintype "passive"))
    )
    (net (code "76") (name "unconnected-(UCVOUT-3-PadP$2)") (class "Default")
      (node (ref "UCVOUT") (pin "P$2") (pinfunction "3_P$2") (pintype "passive"))
    )
    (net (code "77") (name "unconnected-(UFOUT1-3-PadP$2)") (class "Default")
      (node (ref "UFOUT1") (pin "P$2") (pinfunction "3_P$2") (pintype "passive"))
    )
    (net (code "78") (name "unconnected-(UFOUT2-3-PadP$2)") (class "Default")
      (node (ref "UFOUT2") (pin "P$2") (pinfunction "3_P$2") (pintype "passive"))
    )
  )
)
